# DDS.net
KiCad netlist of a schematic drawn in Altium Designer
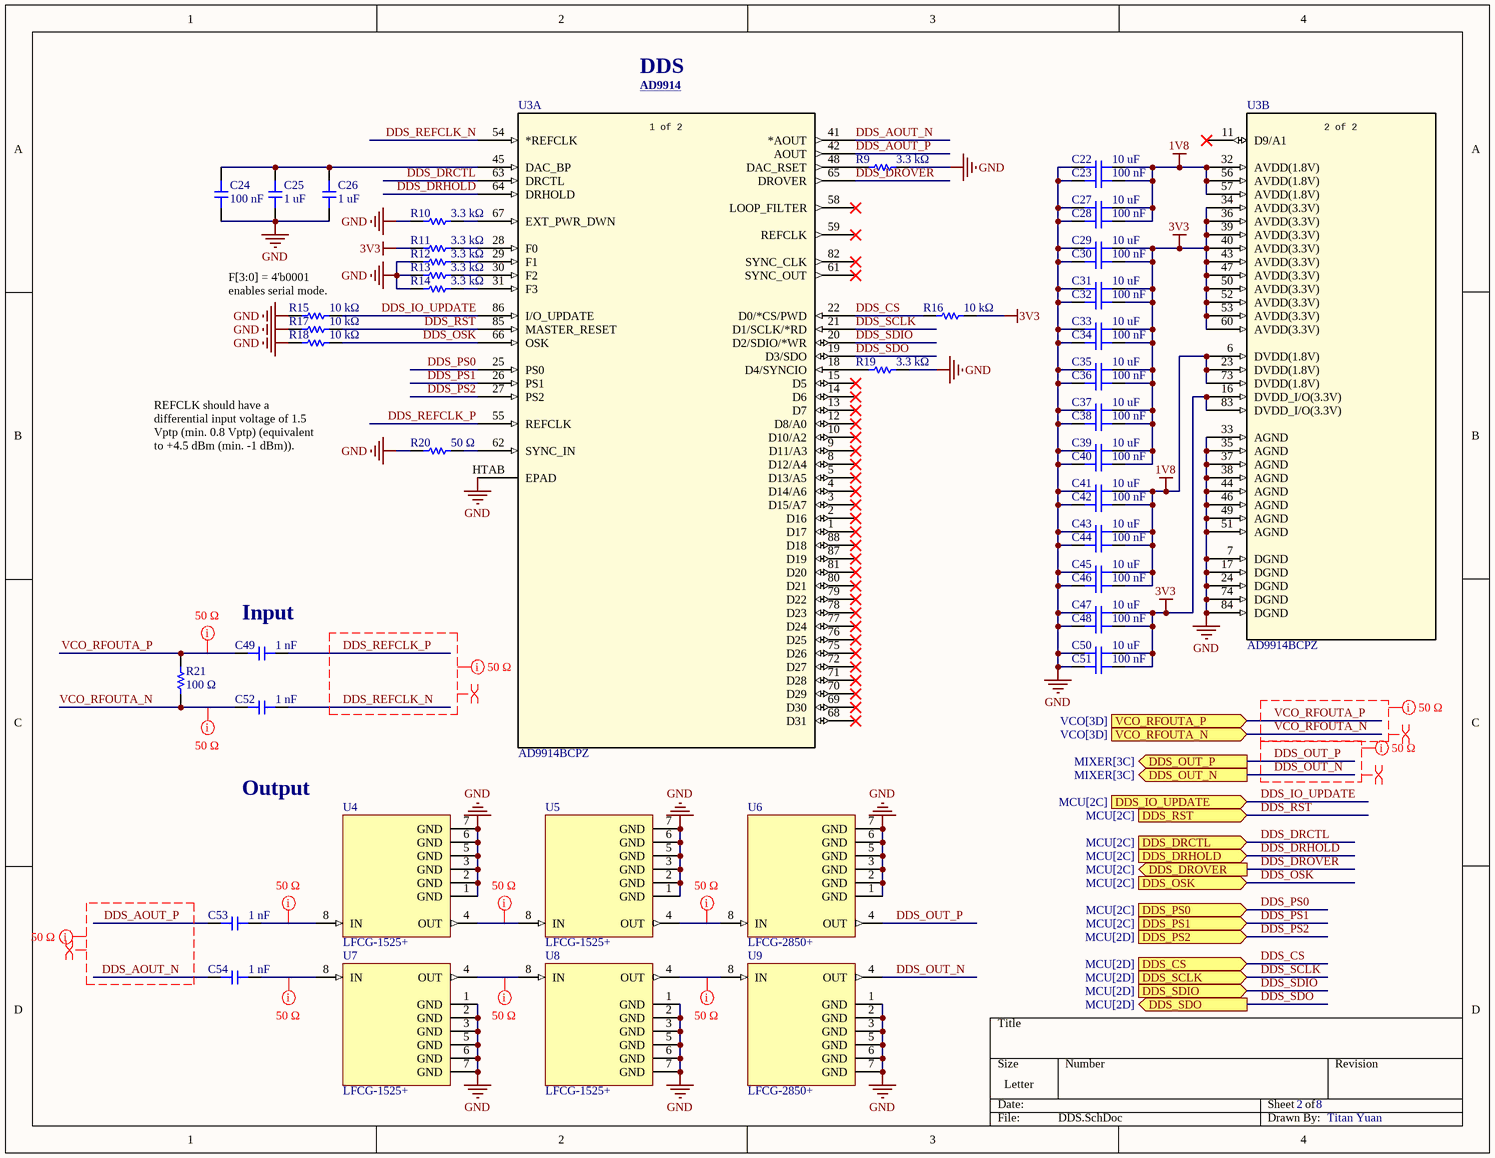
[diagram p0: DDS.SchDoc]

(export (version "E")
  (design (tool "Eeschema 10.0.6"))
  (components
    (comp (ref "C22")
      (value "10 uF")
      (footprint "CAP_0805")
      (description "16V 10uF X7R ±10% 0805 Multilayer Ceramic Capacitors MLCC - SMD/SMT ROHS")
      (fields
        (field (name "MANUFACTURER") "Samsung Electro-Mechanics")
        (field (name "MANUFACTURER PART NUMBER") "CL21B106KOQNNNE")
      )
      (libsource (lib "Titan") (part "CAP"))
    )
    (comp (ref "C23")
      (value "100 nF")
      (footprint "CAP_0402")
      (description "Ceramic Capacitor, Ceramic, 50V, 10% +Tol, 10% -Tol, X7R, 15% TC, 0.1uF, Surface Mount, 0402")
      (fields
        (field (name "MANUFACTURER") "Yageo")
        (field (name "MANUFACTURER PART NUMBER") "CC0402KPX7R9BB104")
      )
      (libsource (lib "Titan") (part "CAP"))
    )
    (comp (ref "C24")
      (value "100 nF")
      (footprint "CAP_0402")
      (description "Ceramic Capacitor, Ceramic, 50V, 10% +Tol, 10% -Tol, X7R, 15% TC, 0.1uF, Surface Mount, 0402")
      (fields
        (field (name "MANUFACTURER") "Yageo")
        (field (name "MANUFACTURER PART NUMBER") "CC0402KPX7R9BB104")
      )
      (libsource (lib "Titan") (part "CAP"))
    )
    (comp (ref "C25")
      (value "1 uF")
      (footprint "CAP_0603")
      (description "25V 1uF X7R ±10% 0603 Multilayer Ceramic Capacitors MLCC - SMD/SMT ROHS")
      (fields
        (field (name "MANUFACTURER") "Samsung Electro-Mechanics")
        (field (name "MANUFACTURER PART NUMBER") "CL10B105KA8NNNC")
      )
      (libsource (lib "Titan") (part "CAP"))
    )
    (comp (ref "C26")
      (value "1 uF")
      (footprint "CAP_0603")
      (description "25V 1uF X7R ±10% 0603 Multilayer Ceramic Capacitors MLCC - SMD/SMT ROHS")
      (fields
        (field (name "MANUFACTURER") "Samsung Electro-Mechanics")
        (field (name "MANUFACTURER PART NUMBER") "CL10B105KA8NNNC")
      )
      (libsource (lib "Titan") (part "CAP"))
    )
    (comp (ref "C27")
      (value "10 uF")
      (footprint "CAP_0805")
      (description "16V 10uF X7R ±10% 0805 Multilayer Ceramic Capacitors MLCC - SMD/SMT ROHS")
      (fields
        (field (name "MANUFACTURER") "Samsung Electro-Mechanics")
        (field (name "MANUFACTURER PART NUMBER") "CL21B106KOQNNNE")
      )
      (libsource (lib "Titan") (part "CAP"))
    )
    (comp (ref "C28")
      (value "100 nF")
      (footprint "CAP_0402")
      (description "Ceramic Capacitor, Ceramic, 50V, 10% +Tol, 10% -Tol, X7R, 15% TC, 0.1uF, Surface Mount, 0402")
      (fields
        (field (name "MANUFACTURER") "Yageo")
        (field (name "MANUFACTURER PART NUMBER") "CC0402KPX7R9BB104")
      )
      (libsource (lib "Titan") (part "CAP"))
    )
    (comp (ref "C29")
      (value "10 uF")
      (footprint "CAP_0805")
      (description "16V 10uF X7R ±10% 0805 Multilayer Ceramic Capacitors MLCC - SMD/SMT ROHS")
      (fields
        (field (name "MANUFACTURER") "Samsung Electro-Mechanics")
        (field (name "MANUFACTURER PART NUMBER") "CL21B106KOQNNNE")
      )
      (libsource (lib "Titan") (part "CAP"))
    )
    (comp (ref "C30")
      (value "100 nF")
      (footprint "CAP_0402")
      (description "Ceramic Capacitor, Ceramic, 50V, 10% +Tol, 10% -Tol, X7R, 15% TC, 0.1uF, Surface Mount, 0402")
      (fields
        (field (name "MANUFACTURER") "Yageo")
        (field (name "MANUFACTURER PART NUMBER") "CC0402KPX7R9BB104")
      )
      (libsource (lib "Titan") (part "CAP"))
    )
    (comp (ref "C31")
      (value "10 uF")
      (footprint "CAP_0805")
      (description "16V 10uF X7R ±10% 0805 Multilayer Ceramic Capacitors MLCC - SMD/SMT ROHS")
      (fields
        (field (name "MANUFACTURER") "Samsung Electro-Mechanics")
        (field (name "MANUFACTURER PART NUMBER") "CL21B106KOQNNNE")
      )
      (libsource (lib "Titan") (part "CAP"))
    )
    (comp (ref "C32")
      (value "100 nF")
      (footprint "CAP_0402")
      (description "Ceramic Capacitor, Ceramic, 50V, 10% +Tol, 10% -Tol, X7R, 15% TC, 0.1uF, Surface Mount, 0402")
      (fields
        (field (name "MANUFACTURER") "Yageo")
        (field (name "MANUFACTURER PART NUMBER") "CC0402KPX7R9BB104")
      )
      (libsource (lib "Titan") (part "CAP"))
    )
    (comp (ref "C33")
      (value "10 uF")
      (footprint "CAP_0805")
      (description "16V 10uF X7R ±10% 0805 Multilayer Ceramic Capacitors MLCC - SMD/SMT ROHS")
      (fields
        (field (name "MANUFACTURER") "Samsung Electro-Mechanics")
        (field (name "MANUFACTURER PART NUMBER") "CL21B106KOQNNNE")
      )
      (libsource (lib "Titan") (part "CAP"))
    )
    (comp (ref "C34")
      (value "100 nF")
      (footprint "CAP_0402")
      (description "Ceramic Capacitor, Ceramic, 50V, 10% +Tol, 10% -Tol, X7R, 15% TC, 0.1uF, Surface Mount, 0402")
      (fields
        (field (name "MANUFACTURER") "Yageo")
        (field (name "MANUFACTURER PART NUMBER") "CC0402KPX7R9BB104")
      )
      (libsource (lib "Titan") (part "CAP"))
    )
    (comp (ref "C35")
      (value "10 uF")
      (footprint "CAP_0805")
      (description "16V 10uF X7R ±10% 0805 Multilayer Ceramic Capacitors MLCC - SMD/SMT ROHS")
      (fields
        (field (name "MANUFACTURER") "Samsung Electro-Mechanics")
        (field (name "MANUFACTURER PART NUMBER") "CL21B106KOQNNNE")
      )
      (libsource (lib "Titan") (part "CAP"))
    )
    (comp (ref "C36")
      (value "100 nF")
      (footprint "CAP_0402")
      (description "Ceramic Capacitor, Ceramic, 50V, 10% +Tol, 10% -Tol, X7R, 15% TC, 0.1uF, Surface Mount, 0402")
      (fields
        (field (name "MANUFACTURER") "Yageo")
        (field (name "MANUFACTURER PART NUMBER") "CC0402KPX7R9BB104")
      )
      (libsource (lib "Titan") (part "CAP"))
    )
    (comp (ref "C37")
      (value "10 uF")
      (footprint "CAP_0805")
      (description "16V 10uF X7R ±10% 0805 Multilayer Ceramic Capacitors MLCC - SMD/SMT ROHS")
      (fields
        (field (name "MANUFACTURER") "Samsung Electro-Mechanics")
        (field (name "MANUFACTURER PART NUMBER") "CL21B106KOQNNNE")
      )
      (libsource (lib "Titan") (part "CAP"))
    )
    (comp (ref "C38")
      (value "100 nF")
      (footprint "CAP_0402")
      (description "Ceramic Capacitor, Ceramic, 50V, 10% +Tol, 10% -Tol, X7R, 15% TC, 0.1uF, Surface Mount, 0402")
      (fields
        (field (name "MANUFACTURER") "Yageo")
        (field (name "MANUFACTURER PART NUMBER") "CC0402KPX7R9BB104")
      )
      (libsource (lib "Titan") (part "CAP"))
    )
    (comp (ref "C39")
      (value "10 uF")
      (footprint "CAP_0805")
      (description "16V 10uF X7R ±10% 0805 Multilayer Ceramic Capacitors MLCC - SMD/SMT ROHS")
      (fields
        (field (name "MANUFACTURER") "Samsung Electro-Mechanics")
        (field (name "MANUFACTURER PART NUMBER") "CL21B106KOQNNNE")
      )
      (libsource (lib "Titan") (part "CAP"))
    )
    (comp (ref "C40")
      (value "100 nF")
      (footprint "CAP_0402")
      (description "Ceramic Capacitor, Ceramic, 50V, 10% +Tol, 10% -Tol, X7R, 15% TC, 0.1uF, Surface Mount, 0402")
      (fields
        (field (name "MANUFACTURER") "Yageo")
        (field (name "MANUFACTURER PART NUMBER") "CC0402KPX7R9BB104")
      )
      (libsource (lib "Titan") (part "CAP"))
    )
    (comp (ref "C41")
      (value "10 uF")
      (footprint "CAP_0805")
      (description "16V 10uF X7R ±10% 0805 Multilayer Ceramic Capacitors MLCC - SMD/SMT ROHS")
      (fields
        (field (name "MANUFACTURER") "Samsung Electro-Mechanics")
        (field (name "MANUFACTURER PART NUMBER") "CL21B106KOQNNNE")
      )
      (libsource (lib "Titan") (part "CAP"))
    )
    (comp (ref "C42")
      (value "100 nF")
      (footprint "CAP_0402")
      (description "Ceramic Capacitor, Ceramic, 50V, 10% +Tol, 10% -Tol, X7R, 15% TC, 0.1uF, Surface Mount, 0402")
      (fields
        (field (name "MANUFACTURER") "Yageo")
        (field (name "MANUFACTURER PART NUMBER") "CC0402KPX7R9BB104")
      )
      (libsource (lib "Titan") (part "CAP"))
    )
    (comp (ref "C43")
      (value "10 uF")
      (footprint "CAP_0805")
      (description "16V 10uF X7R ±10% 0805 Multilayer Ceramic Capacitors MLCC - SMD/SMT ROHS")
      (fields
        (field (name "MANUFACTURER") "Samsung Electro-Mechanics")
        (field (name "MANUFACTURER PART NUMBER") "CL21B106KOQNNNE")
      )
      (libsource (lib "Titan") (part "CAP"))
    )
    (comp (ref "C44")
      (value "100 nF")
      (footprint "CAP_0402")
      (description "Ceramic Capacitor, Ceramic, 50V, 10% +Tol, 10% -Tol, X7R, 15% TC, 0.1uF, Surface Mount, 0402")
      (fields
        (field (name "MANUFACTURER") "Yageo")
        (field (name "MANUFACTURER PART NUMBER") "CC0402KPX7R9BB104")
      )
      (libsource (lib "Titan") (part "CAP"))
    )
    (comp (ref "C45")
      (value "10 uF")
      (footprint "CAP_0805")
      (description "16V 10uF X7R ±10% 0805 Multilayer Ceramic Capacitors MLCC - SMD/SMT ROHS")
      (fields
        (field (name "MANUFACTURER") "Samsung Electro-Mechanics")
        (field (name "MANUFACTURER PART NUMBER") "CL21B106KOQNNNE")
      )
      (libsource (lib "Titan") (part "CAP"))
    )
    (comp (ref "C46")
      (value "100 nF")
      (footprint "CAP_0402")
      (description "Ceramic Capacitor, Ceramic, 50V, 10% +Tol, 10% -Tol, X7R, 15% TC, 0.1uF, Surface Mount, 0402")
      (fields
        (field (name "MANUFACTURER") "Yageo")
        (field (name "MANUFACTURER PART NUMBER") "CC0402KPX7R9BB104")
      )
      (libsource (lib "Titan") (part "CAP"))
    )
    (comp (ref "C47")
      (value "10 uF")
      (footprint "CAP_0805")
      (description "16V 10uF X7R ±10% 0805 Multilayer Ceramic Capacitors MLCC - SMD/SMT ROHS")
      (fields
        (field (name "MANUFACTURER") "Samsung Electro-Mechanics")
        (field (name "MANUFACTURER PART NUMBER") "CL21B106KOQNNNE")
      )
      (libsource (lib "Titan") (part "CAP"))
    )
    (comp (ref "C48")
      (value "100 nF")
      (footprint "CAP_0402")
      (description "Ceramic Capacitor, Ceramic, 50V, 10% +Tol, 10% -Tol, X7R, 15% TC, 0.1uF, Surface Mount, 0402")
      (fields
        (field (name "MANUFACTURER") "Yageo")
        (field (name "MANUFACTURER PART NUMBER") "CC0402KPX7R9BB104")
      )
      (libsource (lib "Titan") (part "CAP"))
    )
    (comp (ref "C49")
      (value "1 nF")
      (footprint "CAP_0402")
      (description "50V 1nF X7R ±10% 0402 Multilayer Ceramic Capacitors MLCC - SMD/SMT ROHS")
      (fields
        (field (name "MANUFACTURER") "Yageo")
        (field (name "MANUFACTURER PART NUMBER") "CC0402KRX7R9BB102")
      )
      (libsource (lib "Titan") (part "CAP"))
    )
    (comp (ref "C50")
      (value "10 uF")
      (footprint "CAP_0805")
      (description "16V 10uF X7R ±10% 0805 Multilayer Ceramic Capacitors MLCC - SMD/SMT ROHS")
      (fields
        (field (name "MANUFACTURER") "Samsung Electro-Mechanics")
        (field (name "MANUFACTURER PART NUMBER") "CL21B106KOQNNNE")
      )
      (libsource (lib "Titan") (part "CAP"))
    )
    (comp (ref "C51")
      (value "100 nF")
      (footprint "CAP_0402")
      (description "Ceramic Capacitor, Ceramic, 50V, 10% +Tol, 10% -Tol, X7R, 15% TC, 0.1uF, Surface Mount, 0402")
      (fields
        (field (name "MANUFACTURER") "Yageo")
        (field (name "MANUFACTURER PART NUMBER") "CC0402KPX7R9BB104")
      )
      (libsource (lib "Titan") (part "CAP"))
    )
    (comp (ref "C52")
      (value "1 nF")
      (footprint "CAP_0402")
      (description "50V 1nF X7R ±10% 0402 Multilayer Ceramic Capacitors MLCC - SMD/SMT ROHS")
      (fields
        (field (name "MANUFACTURER") "Yageo")
        (field (name "MANUFACTURER PART NUMBER") "CC0402KRX7R9BB102")
      )
      (libsource (lib "Titan") (part "CAP"))
    )
    (comp (ref "C53")
      (value "1 nF")
      (footprint "CAP_0402")
      (description "50V 1nF X7R ±10% 0402 Multilayer Ceramic Capacitors MLCC - SMD/SMT ROHS")
      (fields
        (field (name "MANUFACTURER") "Yageo")
        (field (name "MANUFACTURER PART NUMBER") "CC0402KRX7R9BB102")
      )
      (libsource (lib "Titan") (part "CAP"))
    )
    (comp (ref "C54")
      (value "1 nF")
      (footprint "CAP_0402")
      (description "50V 1nF X7R ±10% 0402 Multilayer Ceramic Capacitors MLCC - SMD/SMT ROHS")
      (fields
        (field (name "MANUFACTURER") "Yageo")
        (field (name "MANUFACTURER PART NUMBER") "CC0402KRX7R9BB102")
      )
      (libsource (lib "Titan") (part "CAP"))
    )
    (comp (ref "R9")
      (value "3.3 kΩ")
      (footprint "RES_0402")
      (description "62.5Mw Thick Film Resistors 100Ppm/ 1% 3.3K 0402 Chip Resistor Surface Mount Rohs")
      (fields
        (field (name "MANUFACTURER") "Yageo")
        (field (name "MANUFACTURER PART NUMBER") "RC0402FR-073K3L")
      )
      (libsource (lib "Titan") (part "RES"))
    )
    (comp (ref "R10")
      (value "3.3 kΩ")
      (footprint "RES_0402")
      (description "62.5Mw Thick Film Resistors 100Ppm/ 1% 3.3K 0402 Chip Resistor Surface Mount Rohs")
      (fields
        (field (name "MANUFACTURER") "Yageo")
        (field (name "MANUFACTURER PART NUMBER") "RC0402FR-073K3L")
      )
      (libsource (lib "Titan") (part "RES"))
    )
    (comp (ref "R11")
      (value "3.3 kΩ")
      (footprint "RES_0402")
      (description "62.5Mw Thick Film Resistors 100Ppm/ 1% 3.3K 0402 Chip Resistor Surface Mount Rohs")
      (fields
        (field (name "MANUFACTURER") "Yageo")
        (field (name "MANUFACTURER PART NUMBER") "RC0402FR-073K3L")
      )
      (libsource (lib "Titan") (part "RES"))
    )
    (comp (ref "R12")
      (value "3.3 kΩ")
      (footprint "RES_0402")
      (description "62.5Mw Thick Film Resistors 100Ppm/ 1% 3.3K 0402 Chip Resistor Surface Mount Rohs")
      (fields
        (field (name "MANUFACTURER") "Yageo")
        (field (name "MANUFACTURER PART NUMBER") "RC0402FR-073K3L")
      )
      (libsource (lib "Titan") (part "RES"))
    )
    (comp (ref "R13")
      (value "3.3 kΩ")
      (footprint "RES_0402")
      (description "62.5Mw Thick Film Resistors 100Ppm/ 1% 3.3K 0402 Chip Resistor Surface Mount Rohs")
      (fields
        (field (name "MANUFACTURER") "Yageo")
        (field (name "MANUFACTURER PART NUMBER") "RC0402FR-073K3L")
      )
      (libsource (lib "Titan") (part "RES"))
    )
    (comp (ref "R14")
      (value "3.3 kΩ")
      (footprint "RES_0402")
      (description "62.5Mw Thick Film Resistors 100Ppm/ 1% 3.3K 0402 Chip Resistor Surface Mount Rohs")
      (fields
        (field (name "MANUFACTURER") "Yageo")
        (field (name "MANUFACTURER PART NUMBER") "RC0402FR-073K3L")
      )
      (libsource (lib "Titan") (part "RES"))
    )
    (comp (ref "R15")
      (value "10 kΩ")
      (footprint "RES_0402")
      (description "Res Thick Film 0402 10K Ohm 1% 0.063W(1/16W) ±100ppm/C Pad SMD T/R")
      (fields
        (field (name "MANUFACTURER") "Yageo")
        (field (name "MANUFACTURER PART NUMBER") "RC0402FR-0710KL")
      )
      (libsource (lib "Titan") (part "RES"))
    )
    (comp (ref "R16")
      (value "10 kΩ")
      (footprint "RES_0402")
      (description "Res Thick Film 0402 10K Ohm 1% 0.063W(1/16W) ±100ppm/C Pad SMD T/R")
      (fields
        (field (name "MANUFACTURER") "Yageo")
        (field (name "MANUFACTURER PART NUMBER") "RC0402FR-0710KL")
      )
      (libsource (lib "Titan") (part "RES"))
    )
    (comp (ref "R17")
      (value "10 kΩ")
      (footprint "RES_0402")
      (description "Res Thick Film 0402 10K Ohm 1% 0.063W(1/16W) ±100ppm/C Pad SMD T/R")
      (fields
        (field (name "MANUFACTURER") "Yageo")
        (field (name "MANUFACTURER PART NUMBER") "RC0402FR-0710KL")
      )
      (libsource (lib "Titan") (part "RES"))
    )
    (comp (ref "R18")
      (value "10 kΩ")
      (footprint "RES_0402")
      (description "Res Thick Film 0402 10K Ohm 1% 0.063W(1/16W) ±100ppm/C Pad SMD T/R")
      (fields
        (field (name "MANUFACTURER") "Yageo")
        (field (name "MANUFACTURER PART NUMBER") "RC0402FR-0710KL")
      )
      (libsource (lib "Titan") (part "RES"))
    )
    (comp (ref "R19")
      (value "3.3 kΩ")
      (footprint "RES_0402")
      (description "62.5Mw Thick Film Resistors 100Ppm/ 1% 3.3K 0402 Chip Resistor Surface Mount Rohs")
      (fields
        (field (name "MANUFACTURER") "Yageo")
        (field (name "MANUFACTURER PART NUMBER") "RC0402FR-073K3L")
      )
      (libsource (lib "Titan") (part "RES"))
    )
    (comp (ref "R20")
      (value "50 Ω")
      (footprint "RES_0402")
      (description "62.5mW Thin Film Resistor ±50ppm/℃ ±0.1% 50Ω 0402 Chip Resistor - Surface Mount ROHS")
      (fields
        (field (name "MANUFACTURER") "Yageo")
        (field (name "MANUFACTURER PART NUMBER") "RT0402BRE0750RL")
      )
      (libsource (lib "Titan") (part "RES"))
    )
    (comp (ref "R21")
      (value "100 Ω")
      (footprint "RES_0402")
      (description "62.5mW Thin Film Resistor ±1% ±50ppm/℃ 100Ω 0402 Chip Resistor - Surface Mount ROHS")
      (fields
        (field (name "MANUFACTURER") "Yageo")
        (field (name "MANUFACTURER PART NUMBER") "RT0402FRE07100RL")
      )
      (libsource (lib "Titan") (part "RES"))
    )
    (comp (ref "U3")
      (value "AD9914BCPZ")
      (footprint "CP_88_5_ADI")
      (description "Direct Digital Synthesizer 3500MHz 1-DAC 12-Bit Parallel/Serial 88-Pin LFCSP EP Tray")
      (fields
        (field (name "MANUFACTURER") "Analog Devices")
        (field (name "COPYRIGHT") "Copyright (C) 2026 Ultra Librarian. All rights reserved.")
      )
      (libsource (lib "AD9914BCPZ") (part "AD9914BCPZ"))
    )
    (comp (ref "U4")
      (value "LFCG-1525+")
      (footprint "PL-429")
      (description "Ceramic LPF, 1 Section(s) Min, 1 Section(s) Max")
      (fields (field (name "MANUFACTURER") "Mini-Circuits"))
      (libsource (lib "") (part "LFCG-1525+_1"))
    )
    (comp (ref "U5")
      (value "LFCG-1525+")
      (footprint "PL-429")
      (description "Ceramic LPF, 1 Section(s) Min, 1 Section(s) Max")
      (fields (field (name "MANUFACTURER") "Mini-Circuits"))
      (libsource (lib "") (part "LFCG-1525+_1"))
    )
    (comp (ref "U6")
      (value "LFCG-2850+")
      (footprint "PL-429")
      (description "1.8dB 50Ω 2.85GHz 0805 SMD mount 2mm*1.25mm*950μm")
      (fields (field (name "MANUFACTURER") "Mini-Circuits"))
      (libsource (lib "Titan") (part "LFCG-2850+"))
    )
    (comp (ref "U7")
      (value "LFCG-1525+")
      (footprint "PL-429")
      (description "Ceramic LPF, 1 Section(s) Min, 1 Section(s) Max")
      (fields (field (name "MANUFACTURER") "Mini-Circuits"))
      (libsource (lib "Titan") (part "LFCG-1525+"))
    )
    (comp (ref "U8")
      (value "LFCG-1525+")
      (footprint "PL-429")
      (description "Ceramic LPF, 1 Section(s) Min, 1 Section(s) Max")
      (fields (field (name "MANUFACTURER") "Mini-Circuits"))
      (libsource (lib "Titan") (part "LFCG-1525+"))
    )
    (comp (ref "U9")
      (value "LFCG-2850+")
      (footprint "PL-429")
      (description "1.8dB 50Ω 2.85GHz 0805 SMD mount 2mm*1.25mm*950μm")
      (fields (field (name "MANUFACTURER") "Mini-Circuits"))
      (libsource (lib "") (part "LFCG-2850+_1"))
    )
  )
  (nets
    (net (code "1") (name "/DDS_AOUT_N") (class "Default")
      (node (ref "C54") (pin "2") (pintype "passive"))
      (node (ref "U3") (pin "41") (pinfunction "*AOUT_41") (pintype "output"))
    )
    (net (code "2") (name "/DDS_AOUT_P") (class "Default")
      (node (ref "C53") (pin "2") (pintype "passive"))
      (node (ref "U3") (pin "42") (pinfunction "AOUT_42") (pintype "output"))
    )
    (net (code "3") (name "/DDS_CS") (class "Default")
      (node (ref "R16") (pin "2") (pintype "passive"))
      (node (ref "U3") (pin "22") (pinfunction "D0/*CS/PWD_22") (pintype "input"))
    )
    (net (code "4") (name "/DDS_DRCTL") (class "Default")
      (node (ref "U3") (pin "63") (pinfunction "DRCTL_63") (pintype "input"))
    )
    (net (code "5") (name "/DDS_DRHOLD") (class "Default")
      (node (ref "U3") (pin "64") (pinfunction "DRHOLD_64") (pintype "input"))
    )
    (net (code "6") (name "/DDS_DROVER") (class "Default")
      (node (ref "U3") (pin "65") (pinfunction "DROVER_65") (pintype "output"))
    )
    (net (code "7") (name "/DDS_IO_UPDATE") (class "Default")
      (node (ref "R15") (pin "2") (pintype "passive"))
      (node (ref "U3") (pin "86") (pinfunction "I/O_UPDATE_86") (pintype "input"))
    )
    (net (code "8") (name "/DDS_OSK") (class "Default")
      (node (ref "R18") (pin "2") (pintype "passive"))
      (node (ref "U3") (pin "66") (pinfunction "OSK_66") (pintype "input"))
    )
    (net (code "9") (name "/DDS_OUT_N") (class "Default")
      (node (ref "U9") (pin "4") (pinfunction "OUT_4") (pintype "output"))
    )
    (net (code "10") (name "/DDS_OUT_P") (class "Default")
      (node (ref "U6") (pin "4") (pinfunction "OUT_4") (pintype "output"))
    )
    (net (code "11") (name "/DDS_PS0") (class "Default")
      (node (ref "U3") (pin "25") (pinfunction "PS0_25") (pintype "input"))
    )
    (net (code "12") (name "/DDS_PS1") (class "Default")
      (node (ref "U3") (pin "26") (pinfunction "PS1_26") (pintype "input"))
    )
    (net (code "13") (name "/DDS_PS2") (class "Default")
      (node (ref "U3") (pin "27") (pinfunction "PS2_27") (pintype "input"))
    )
    (net (code "14") (name "/DDS_REFCLK_N") (class "Default")
      (node (ref "C52") (pin "1") (pintype "passive"))
      (node (ref "U3") (pin "54") (pinfunction "*REFCLK_54") (pintype "input"))
    )
    (net (code "15") (name "/DDS_REFCLK_P") (class "Default")
      (node (ref "C49") (pin "1") (pintype "passive"))
      (node (ref "U3") (pin "55") (pinfunction "REFCLK_55") (pintype "input"))
    )
    (net (code "16") (name "/DDS_RST") (class "Default")
      (node (ref "R17") (pin "2") (pintype "passive"))
      (node (ref "U3") (pin "85") (pinfunction "MASTER_RESET_85") (pintype "input"))
    )
    (net (code "17") (name "/DDS_SCLK") (class "Default")
      (node (ref "U3") (pin "21") (pinfunction "D1/SCLK/*RD_21") (pintype "input"))
    )
    (net (code "18") (name "/DDS_SDIO") (class "Default")
      (node (ref "U3") (pin "20") (pinfunction "D2/SDIO/*WR_20") (pintype "bidirectional"))
    )
    (net (code "19") (name "/DDS_SDO") (class "Default")
      (node (ref "U3") (pin "19") (pinfunction "D3/SDO_19") (pintype "bidirectional"))
    )
    (net (code "20") (name "/VCO_RFOUTA_N") (class "Default")
      (node (ref "C52") (pin "2") (pintype "passive"))
      (node (ref "R21") (pin "1") (pintype "passive"))
    )
    (net (code "21") (name "/VCO_RFOUTA_P") (class "Default")
      (node (ref "C49") (pin "2") (pintype "passive"))
      (node (ref "R21") (pin "2") (pintype "passive"))
    )
    (net (code "22") (name "1V8") (class "Default")
      (node (ref "C22") (pin "2") (pintype "passive"))
      (node (ref "C23") (pin "2") (pintype "passive"))
      (node (ref "C27") (pin "2") (pintype "passive"))
      (node (ref "C28") (pin "2") (pintype "passive"))
      (node (ref "C41") (pin "2") (pintype "passive"))
      (node (ref "C42") (pin "2") (pintype "passive"))
      (node (ref "C43") (pin "2") (pintype "passive"))
      (node (ref "C44") (pin "2") (pintype "passive"))
      (node (ref "C45") (pin "2") (pintype "passive"))
      (node (ref "C46") (pin "2") (pintype "passive"))
      (node (ref "U3") (pin "23") (pinfunction "DVDD(1.8V)_23") (pintype "input"))
      (node (ref "U3") (pin "32") (pinfunction "AVDD(1.8V)_32") (pintype "input"))
      (node (ref "U3") (pin "56") (pinfunction "AVDD(1.8V)_56") (pintype "input"))
      (node (ref "U3") (pin "57") (pinfunction "AVDD(1.8V)_57") (pintype "input"))
      (node (ref "U3") (pin "6") (pinfunction "DVDD(1.8V)_6") (pintype "input"))
      (node (ref "U3") (pin "73") (pinfunction "DVDD(1.8V)_73") (pintype "input"))
    )
    (net (code "23") (name "3V3") (class "Default")
      (node (ref "C29") (pin "2") (pintype "passive"))
      (node (ref "C30") (pin "2") (pintype "passive"))
      (node (ref "C31") (pin "2") (pintype "passive"))
      (node (ref "C32") (pin "2") (pintype "passive"))
      (node (ref "C33") (pin "2") (pintype "passive"))
      (node (ref "C34") (pin "2") (pintype "passive"))
      (node (ref "C35") (pin "2") (pintype "passive"))
      (node (ref "C36") (pin "2") (pintype "passive"))
      (node (ref "C37") (pin "2") (pintype "passive"))
      (node (ref "C38") (pin "2") (pintype "passive"))
      (node (ref "C39") (pin "2") (pintype "passive"))
      (node (ref "C40") (pin "2") (pintype "passive"))
      (node (ref "C47") (pin "2") (pintype "passive"))
      (node (ref "C48") (pin "2") (pintype "passive"))
      (node (ref "C50") (pin "2") (pintype "passive"))
      (node (ref "C51") (pin "2") (pintype "passive"))
      (node (ref "R11") (pin "2") (pintype "passive"))
      (node (ref "R16") (pin "1") (pintype "passive"))
      (node (ref "U3") (pin "16") (pinfunction "DVDD_I/O(3.3V)_16") (pintype "input"))
      (node (ref "U3") (pin "34") (pinfunction "AVDD(3.3V)_34") (pintype "input"))
      (node (ref "U3") (pin "36") (pinfunction "AVDD(3.3V)_36") (pintype "input"))
      (node (ref "U3") (pin "39") (pinfunction "AVDD(3.3V)_39") (pintype "input"))
      (node (ref "U3") (pin "40") (pinfunction "AVDD(3.3V)_40") (pintype "input"))
      (node (ref "U3") (pin "43") (pinfunction "AVDD(3.3V)_43") (pintype "input"))
      (node (ref "U3") (pin "47") (pinfunction "AVDD(3.3V)_47") (pintype "input"))
      (node (ref "U3") (pin "50") (pinfunction "AVDD(3.3V)_50") (pintype "input"))
      (node (ref "U3") (pin "52") (pinfunction "AVDD(3.3V)_52") (pintype "input"))
      (node (ref "U3") (pin "53") (pinfunction "AVDD(3.3V)_53") (pintype "input"))
      (node (ref "U3") (pin "60") (pinfunction "AVDD(3.3V)_60") (pintype "input"))
      (node (ref "U3") (pin "83") (pinfunction "DVDD_I/O(3.3V)_83") (pintype "input"))
    )
    (net (code "24") (name "GND") (class "Default")
      (node (ref "C22") (pin "1") (pintype "passive"))
      (node (ref "C23") (pin "1") (pintype "passive"))
      (node (ref "C24") (pin "2") (pintype "passive"))
      (node (ref "C25") (pin "2") (pintype "passive"))
      (node (ref "C26") (pin "2") (pintype "passive"))
      (node (ref "C27") (pin "1") (pintype "passive"))
      (node (ref "C28") (pin "1") (pintype "passive"))
      (node (ref "C29") (pin "1") (pintype "passive"))
      (node (ref "C30") (pin "1") (pintype "passive"))
      (node (ref "C31") (pin "1") (pintype "passive"))
      (node (ref "C32") (pin "1") (pintype "passive"))
      (node (ref "C33") (pin "1") (pintype "passive"))
      (node (ref "C34") (pin "1") (pintype "passive"))
      (node (ref "C35") (pin "1") (pintype "passive"))
      (node (ref "C36") (pin "1") (pintype "passive"))
      (node (ref "C37") (pin "1") (pintype "passive"))
      (node (ref "C38") (pin "1") (pintype "passive"))
      (node (ref "C39") (pin "1") (pintype "passive"))
      (node (ref "C40") (pin "1") (pintype "passive"))
      (node (ref "C41") (pin "1") (pintype "passive"))
      (node (ref "C42") (pin "1") (pintype "passive"))
      (node (ref "C43") (pin "1") (pintype "passive"))
      (node (ref "C44") (pin "1") (pintype "passive"))
      (node (ref "C45") (pin "1") (pintype "passive"))
      (node (ref "C46") (pin "1") (pintype "passive"))
      (node (ref "C47") (pin "1") (pintype "passive"))
      (node (ref "C48") (pin "1") (pintype "passive"))
      (node (ref "C50") (pin "1") (pintype "passive"))
      (node (ref "C51") (pin "1") (pintype "passive"))
      (node (ref "R10") (pin "2") (pintype "passive"))
      (node (ref "R12") (pin "2") (pintype "passive"))
      (node (ref "R13") (pin "2") (pintype "passive"))
      (node (ref "R14") (pin "2") (pintype "passive"))
      (node (ref "R15") (pin "1") (pintype "passive"))
      (node (ref "R17") (pin "1") (pintype "passive"))
      (node (ref "R18") (pin "1") (pintype "passive"))
      (node (ref "R19") (pin "1") (pintype "passive"))
      (node (ref "R20") (pin "2") (pintype "passive"))
      (node (ref "R9") (pin "1") (pintype "passive"))
      (node (ref "U3") (pin "17") (pinfunction "DGND_17") (pintype "input"))
      (node (ref "U3") (pin "24") (pinfunction "DGND_24") (pintype "input"))
      (node (ref "U3") (pin "33") (pinfunction "AGND_33") (pintype "input"))
      (node (ref "U3") (pin "35") (pinfunction "AGND_35") (pintype "input"))
      (node (ref "U3") (pin "37") (pinfunction "AGND_37") (pintype "input"))
      (node (ref "U3") (pin "38") (pinfunction "AGND_38") (pintype "input"))
      (node (ref "U3") (pin "44") (pinfunction "AGND_44") (pintype "input"))
      (node (ref "U3") (pin "46") (pinfunction "AGND_46") (pintype "input"))
      (node (ref "U3") (pin "49") (pinfunction "AGND_49") (pintype "input"))
      (node (ref "U3") (pin "51") (pinfunction "AGND_51") (pintype "input"))
      (node (ref "U3") (pin "7") (pinfunction "DGND_7") (pintype "input"))
      (node (ref "U3") (pin "74") (pinfunction "DGND_74") (pintype "input"))
      (node (ref "U3") (pin "84") (pinfunction "DGND_84") (pintype "input"))
      (node (ref "U3") (pin "HTAB") (pinfunction "EPAD_HTAB") (pintype "passive"))
      (node (ref "U4") (pin "1") (pinfunction "GND_1") (pintype "power_in"))
      (node (ref "U4") (pin "2") (pinfunction "GND_2") (pintype "power_in"))
      (node (ref "U4") (pin "3") (pinfunction "GND_3") (pintype "power_in"))
      (node (ref "U4") (pin "5") (pinfunction "GND_5") (pintype "power_in"))
      (node (ref "U4") (pin "6") (pinfunction "GND_6") (pintype "power_in"))
      (node (ref "U4") (pin "7") (pinfunction "GND_7") (pintype "power_in"))
      (node (ref "U5") (pin "1") (pinfunction "GND_1") (pintype "power_in"))
      (node (ref "U5") (pin "2") (pinfunction "GND_2") (pintype "power_in"))
      (node (ref "U5") (pin "3") (pinfunction "GND_3") (pintype "power_in"))
      (node (ref "U5") (pin "5") (pinfunction "GND_5") (pintype "power_in"))
      (node (ref "U5") (pin "6") (pinfunction "GND_6") (pintype "power_in"))
      (node (ref "U5") (pin "7") (pinfunction "GND_7") (pintype "power_in"))
      (node (ref "U6") (pin "1") (pinfunction "GND_1") (pintype "power_in"))
      (node (ref "U6") (pin "2") (pinfunction "GND_2") (pintype "power_in"))
      (node (ref "U6") (pin "3") (pinfunction "GND_3") (pintype "power_in"))
      (node (ref "U6") (pin "5") (pinfunction "GND_5") (pintype "power_in"))
      (node (ref "U6") (pin "6") (pinfunction "GND_6") (pintype "power_in"))
      (node (ref "U6") (pin "7") (pinfunction "GND_7") (pintype "power_in"))
      (node (ref "U7") (pin "1") (pinfunction "GND_1") (pintype "power_in"))
      (node (ref "U7") (pin "2") (pinfunction "GND_2") (pintype "power_in"))
      (node (ref "U7") (pin "3") (pinfunction "GND_3") (pintype "power_in"))
      (node (ref "U7") (pin "5") (pinfunction "GND_5") (pintype "power_in"))
      (node (ref "U7") (pin "6") (pinfunction "GND_6") (pintype "power_in"))
      (node (ref "U7") (pin "7") (pinfunction "GND_7") (pintype "power_in"))
      (node (ref "U8") (pin "1") (pinfunction "GND_1") (pintype "power_in"))
      (node (ref "U8") (pin "2") (pinfunction "GND_2") (pintype "power_in"))
      (node (ref "U8") (pin "3") (pinfunction "GND_3") (pintype "power_in"))
      (node (ref "U8") (pin "5") (pinfunction "GND_5") (pintype "power_in"))
      (node (ref "U8") (pin "6") (pinfunction "GND_6") (pintype "power_in"))
      (node (ref "U8") (pin "7") (pinfunction "GND_7") (pintype "power_in"))
      (node (ref "U9") (pin "1") (pinfunction "GND_1") (pintype "power_in"))
      (node (ref "U9") (pin "2") (pinfunction "GND_2") (pintype "power_in"))
      (node (ref "U9") (pin "3") (pinfunction "GND_3") (pintype "power_in"))
      (node (ref "U9") (pin "5") (pinfunction "GND_5") (pintype "power_in"))
      (node (ref "U9") (pin "6") (pinfunction "GND_6") (pintype "power_in"))
      (node (ref "U9") (pin "7") (pinfunction "GND_7") (pintype "power_in"))
    )
    (net (code "25") (name "Net-(U3A-D4{slash}SYNCIO)") (class "Default")
      (node (ref "R19") (pin "2") (pintype "passive"))
      (node (ref "U3") (pin "18") (pinfunction "D4/SYNCIO_18") (pintype "input"))
    )
    (net (code "26") (name "Net-(U3A-DAC_BP)") (class "Default")
      (node (ref "C24") (pin "1") (pintype "passive"))
      (node (ref "C25") (pin "1") (pintype "passive"))
      (node (ref "C26") (pin "1") (pintype "passive"))
      (node (ref "U3") (pin "45") (pinfunction "DAC_BP_45") (pintype "input"))
    )
    (net (code "27") (name "Net-(U3A-DAC_RSET)") (class "Default")
      (node (ref "R9") (pin "2") (pintype "passive"))
      (node (ref "U3") (pin "48") (pinfunction "DAC_RSET_48") (pintype "output"))
    )
    (net (code "28") (name "Net-(U3A-EXT_PWR_DWN)") (class "Default")
      (node (ref "R10") (pin "1") (pintype "passive"))
      (node (ref "U3") (pin "67") (pinfunction "EXT_PWR_DWN_67") (pintype "input"))
    )
    (net (code "29") (name "Net-(U3A-F0)") (class "Default")
      (node (ref "R11") (pin "1") (pintype "passive"))
      (node (ref "U3") (pin "28") (pinfunction "F0_28") (pintype "input"))
    )
    (net (code "30") (name "Net-(U3A-F1)") (class "Default")
      (node (ref "R12") (pin "1") (pintype "passive"))
      (node (ref "U3") (pin "29") (pinfunction "F1_29") (pintype "input"))
    )
    (net (code "31") (name "Net-(U3A-F2)") (class "Default")
      (node (ref "R13") (pin "1") (pintype "passive"))
      (node (ref "U3") (pin "30") (pinfunction "F2_30") (pintype "input"))
    )
    (net (code "32") (name "Net-(U3A-F3)") (class "Default")
      (node (ref "R14") (pin "1") (pintype "passive"))
      (node (ref "U3") (pin "31") (pinfunction "F3_31") (pintype "input"))
    )
    (net (code "33") (name "Net-(U3A-SYNC_IN)") (class "Default")
      (node (ref "R20") (pin "1") (pintype "passive"))
      (node (ref "U3") (pin "62") (pinfunction "SYNC_IN_62") (pintype "input"))
    )
    (net (code "34") (name "Net-(U4-IN)") (class "Default")
      (node (ref "C53") (pin "1") (pintype "passive"))
      (node (ref "U4") (pin "8") (pinfunction "IN_8") (pintype "input"))
    )
    (net (code "35") (name "Net-(U4-OUT)") (class "Default")
      (node (ref "U4") (pin "4") (pinfunction "OUT_4") (pintype "output"))
      (node (ref "U5") (pin "8") (pinfunction "IN_8") (pintype "input"))
    )
    (net (code "36") (name "Net-(U5-OUT)") (class "Default")
      (node (ref "U5") (pin "4") (pinfunction "OUT_4") (pintype "output"))
      (node (ref "U6") (pin "8") (pinfunction "IN_8") (pintype "input"))
    )
    (net (code "37") (name "Net-(U7-IN)") (class "Default")
      (node (ref "C54") (pin "1") (pintype "passive"))
      (node (ref "U7") (pin "8") (pinfunction "IN_8") (pintype "input"))
    )
    (net (code "38") (name "Net-(U7-OUT)") (class "Default")
      (node (ref "U7") (pin "4") (pinfunction "OUT_4") (pintype "output"))
      (node (ref "U8") (pin "8") (pinfunction "IN_8") (pintype "input"))
    )
    (net (code "39") (name "Net-(U8-OUT)") (class "Default")
      (node (ref "U8") (pin "4") (pinfunction "OUT_4") (pintype "output"))
      (node (ref "U9") (pin "8") (pinfunction "IN_8") (pintype "input"))
    )
    (net (code "40") (name "unconnected-(U3A-D5-Pad15)") (class "Default")
      (node (ref "U3") (pin "15") (pinfunction "D5_15") (pintype "bidirectional+no_connect"))
    )
    (net (code "41") (name "unconnected-(U3A-D6-Pad14)") (class "Default")
      (node (ref "U3") (pin "14") (pinfunction "D6_14") (pintype "bidirectional+no_connect"))
    )
    (net (code "42") (name "unconnected-(U3A-D7-Pad13)") (class "Default")
      (node (ref "U3") (pin "13") (pinfunction "D7_13") (pintype "bidirectional+no_connect"))
    )
    (net (code "43") (name "unconnected-(U3A-D8{slash}A0-Pad12)") (class "Default")
      (node (ref "U3") (pin "12") (pinfunction "D8/A0_12") (pintype "bidirectional+no_connect"))
    )
    (net (code "44") (name "unconnected-(U3A-D10{slash}A2-Pad10)") (class "Default")
      (node (ref "U3") (pin "10") (pinfunction "D10/A2_10") (pintype "bidirectional+no_connect"))
    )
    (net (code "45") (name "unconnected-(U3A-D11{slash}A3-Pad9)") (class "Default")
      (node (ref "U3") (pin "9") (pinfunction "D11/A3_9") (pintype "bidirectional+no_connect"))
    )
    (net (code "46") (name "unconnected-(U3A-D12{slash}A4-Pad8)") (class "Default")
      (node (ref "U3") (pin "8") (pinfunction "D12/A4_8") (pintype "bidirectional+no_connect"))
    )
    (net (code "47") (name "unconnected-(U3A-D13{slash}A5-Pad5)") (class "Default")
      (node (ref "U3") (pin "5") (pinfunction "D13/A5_5") (pintype "bidirectional+no_connect"))
    )
    (net (code "48") (name "unconnected-(U3A-D14{slash}A6-Pad4)") (class "Default")
      (node (ref "U3") (pin "4") (pinfunction "D14/A6_4") (pintype "bidirectional+no_connect"))
    )
    (net (code "49") (name "unconnected-(U3A-D15{slash}A7-Pad3)") (class "Default")
      (node (ref "U3") (pin "3") (pinfunction "D15/A7_3") (pintype "bidirectional+no_connect"))
    )
    (net (code "50") (name "unconnected-(U3A-D16-Pad2)") (class "Default")
      (node (ref "U3") (pin "2") (pinfunction "D16_2") (pintype "bidirectional+no_connect"))
    )
    (net (code "51") (name "unconnected-(U3A-D17-Pad1)") (class "Default")
      (node (ref "U3") (pin "1") (pinfunction "D17_1") (pintype "bidirectional+no_connect"))
    )
    (net (code "52") (name "unconnected-(U3A-D18-Pad88)") (class "Default")
      (node (ref "U3") (pin "88") (pinfunction "D18_88") (pintype "bidirectional+no_connect"))
    )
    (net (code "53") (name "unconnected-(U3A-D19-Pad87)") (class "Default")
      (node (ref "U3") (pin "87") (pinfunction "D19_87") (pintype "bidirectional+no_connect"))
    )
    (net (code "54") (name "unconnected-(U3A-D20-Pad81)") (class "Default")
      (node (ref "U3") (pin "81") (pinfunction "D20_81") (pintype "bidirectional+no_connect"))
    )
    (net (code "55") (name "unconnected-(U3A-D21-Pad80)") (class "Default")
      (node (ref "U3") (pin "80") (pinfunction "D21_80") (pintype "bidirectional+no_connect"))
    )
    (net (code "56") (name "unconnected-(U3A-D22-Pad79)") (class "Default")
      (node (ref "U3") (pin "79") (pinfunction "D22_79") (pintype "bidirectional+no_connect"))
    )
    (net (code "57") (name "unconnected-(U3A-D23-Pad78)") (class "Default")
      (node (ref "U3") (pin "78") (pinfunction "D23_78") (pintype "bidirectional+no_connect"))
    )
    (net (code "58") (name "unconnected-(U3A-D24-Pad77)") (class "Default")
      (node (ref "U3") (pin "77") (pinfunction "D24_77") (pintype "bidirectional+no_connect"))
    )
    (net (code "59") (name "unconnected-(U3A-D25-Pad76)") (class "Default")
      (node (ref "U3") (pin "76") (pinfunction "D25_76") (pintype "bidirectional+no_connect"))
    )
    (net (code "60") (name "unconnected-(U3A-D26-Pad75)") (class "Default")
      (node (ref "U3") (pin "75") (pinfunction "D26_75") (pintype "bidirectional+no_connect"))
    )
    (net (code "61") (name "unconnected-(U3A-D27-Pad72)") (class "Default")
      (node (ref "U3") (pin "72") (pinfunction "D27_72") (pintype "bidirectional+no_connect"))
    )
    (net (code "62") (name "unconnected-(U3A-D28-Pad71)") (class "Default")
      (node (ref "U3") (pin "71") (pinfunction "D28_71") (pintype "bidirectional+no_connect"))
    )
    (net (code "63") (name "unconnected-(U3A-D29-Pad70)") (class "Default")
      (node (ref "U3") (pin "70") (pinfunction "D29_70") (pintype "bidirectional+no_connect"))
    )
    (net (code "64") (name "unconnected-(U3A-D30-Pad69)") (class "Default")
      (node (ref "U3") (pin "69") (pinfunction "D30_69") (pintype "bidirectional+no_connect"))
    )
    (net (code "65") (name "unconnected-(U3A-D31-Pad68)") (class "Default")
      (node (ref "U3") (pin "68") (pinfunction "D31_68") (pintype "bidirectional+no_connect"))
    )
    (net (code "66") (name "unconnected-(U3A-LOOP_FILTER-Pad58)") (class "Default")
      (node (ref "U3") (pin "58") (pinfunction "LOOP_FILTER_58") (pintype "output+no_connect"))
    )
    (net (code "67") (name "unconnected-(U3A-REFCLK-Pad59)") (class "Default")
      (node (ref "U3") (pin "59") (pinfunction "REFCLK_59") (pintype "output+no_connect"))
    )
    (net (code "68") (name "unconnected-(U3A-SYNC_CLK-Pad82)") (class "Default")
      (node (ref "U3") (pin "82") (pinfunction "SYNC_CLK_82") (pintype "output+no_connect"))
    )
    (net (code "69") (name "unconnected-(U3A-SYNC_OUT-Pad61)") (class "Default")
      (node (ref "U3") (pin "61") (pinfunction "SYNC_OUT_61") (pintype "output+no_connect"))
    )
    (net (code "70") (name "unconnected-(U3B-D9{slash}A1-Pad11)") (class "Default")
      (node (ref "U3") (pin "11") (pinfunction "D9/A1_11") (pintype "bidirectional+no_connect"))
    )
  )
)
